# v5-Relay-Section-temp.net
KiCad netlist of a schematic drawn in EAGLE
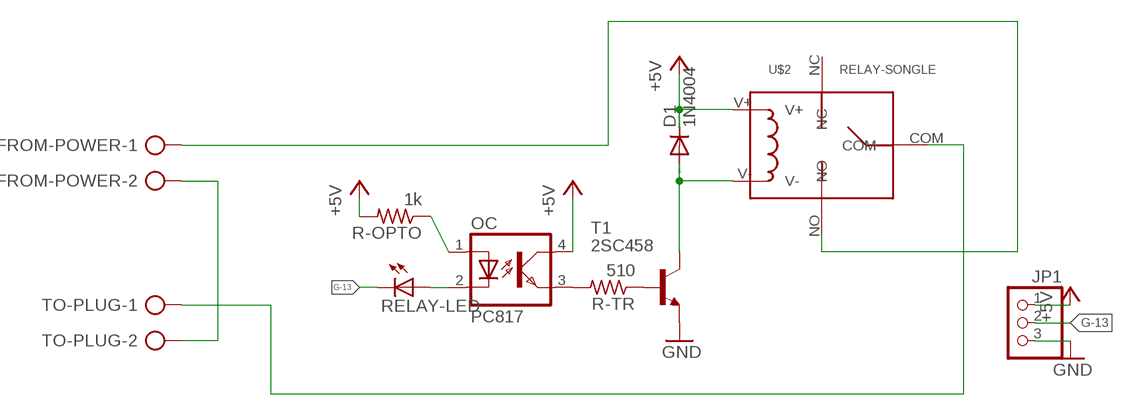
[diagram p0: schematic, sheet 1]

(export (version "E")
  (design (tool "Eeschema 10.0.6"))
  (components
    (comp (ref "D1")
      (value "1N4004")
      (footprint "eagle-import:DO41-10")
      (libsource (lib "eagle-import") (part "1N4004"))
    )
    (comp (ref "FROM-POWER")
      (value "AK300/2")
      (footprint "eagle-import:AK300_2")
      (libsource (lib "eagle-import") (part "AK300/2"))
    )
    (comp (ref "JP1")
      (value "PINHD-1X3")
      (footprint "eagle-import:1X03")
      (libsource (lib "eagle-import") (part "PINHD-1X3"))
    )
    (comp (ref "OC")
      (value "PC817")
      (footprint "eagle-import:DIL04")
      (fields (field (name "MPN") "PC817X4J000F"))
      (libsource (lib "eagle-import") (part "PC817"))
    )
    (comp (ref "R-OPTO")
      (value "1k")
      (footprint "eagle-import:0207_7")
      (libsource (lib "eagle-import") (part "R-US_0207/7"))
    )
    (comp (ref "R-TR")
      (value "510")
      (footprint "eagle-import:0207_7")
      (libsource (lib "eagle-import") (part "R-US_0207/7"))
    )
    (comp (ref "RELAY-LED")
      (value "LED3MM")
      (footprint "eagle-import:LED3MM")
      (libsource (lib "eagle-import") (part "LED3MM"))
    )
    (comp (ref "T1")
      (value "2SC458")
      (footprint "eagle-import:TO92-ECB")
      (libsource (lib "eagle-import") (part "2SC458"))
    )
    (comp (ref "TO-PLUG")
      (value "AK300/2")
      (footprint "eagle-import:AK300_2")
      (libsource (lib "eagle-import") (part "AK300/2"))
    )
    (comp (ref "U$2")
      (value "RELAY-SONGLE")
      (footprint "eagle-import:RELAY-SONGLE")
      (libsource (lib "eagle-import") (part "RELAY-SONGLE"))
    )
  )
  (nets
    (net (code "1") (name "+5V") (class "Default")
      (node (ref "D1") (pin "C") (pinfunction "C_C") (pintype "passive"))
      (node (ref "JP1") (pin "1") (pinfunction "1_1") (pintype "passive"))
      (node (ref "OC") (pin "4") (pinfunction "COL_4") (pintype "passive"))
      (node (ref "R-OPTO") (pin "2") (pinfunction "2_2") (pintype "passive"))
      (node (ref "U$2") (pin "V+") (pinfunction "V+_V+") (pintype "bidirectional"))
    )
    (net (code "2") (name "G-13") (class "Default")
      (node (ref "JP1") (pin "2") (pinfunction "2_2") (pintype "passive"))
      (node (ref "RELAY-LED") (pin "K") (pinfunction "C_K") (pintype "passive"))
    )
    (net (code "3") (name "GND") (class "Default")
      (node (ref "JP1") (pin "3") (pinfunction "3_3") (pintype "passive"))
      (node (ref "T1") (pin "E") (pinfunction "E_E") (pintype "passive"))
    )
    (net (code "4") (name "Net-(D1-PadA)") (class "Default")
      (node (ref "D1") (pin "A") (pinfunction "A_A") (pintype "passive"))
      (node (ref "T1") (pin "C") (pinfunction "C_C") (pintype "passive"))
      (node (ref "U$2") (pin "V-") (pinfunction "V-_V-") (pintype "bidirectional"))
    )
    (net (code "5") (name "Net-(FROM-POWERA-KL)") (class "Default")
      (node (ref "FROM-POWER") (pin "1") (pinfunction "KL_1") (pintype "passive"))
      (node (ref "U$2") (pin "NO") (pinfunction "NO_NO") (pintype "bidirectional"))
    )
    (net (code "6") (name "Net-(FROM-POWERB-KL)") (class "Default")
      (node (ref "FROM-POWER") (pin "2") (pinfunction "KL_2") (pintype "passive"))
      (node (ref "TO-PLUG") (pin "2") (pinfunction "KL_2") (pintype "passive"))
    )
    (net (code "7") (name "Net-(OC-A)") (class "Default")
      (node (ref "OC") (pin "1") (pinfunction "A_1") (pintype "passive"))
      (node (ref "R-OPTO") (pin "1") (pinfunction "1_1") (pintype "passive"))
    )
    (net (code "8") (name "Net-(OC-C)") (class "Default")
      (node (ref "OC") (pin "2") (pinfunction "C_2") (pintype "passive"))
      (node (ref "RELAY-LED") (pin "A") (pinfunction "A_A") (pintype "passive"))
    )
    (net (code "9") (name "Net-(OC-EMIT)") (class "Default")
      (node (ref "OC") (pin "3") (pinfunction "EMIT_3") (pintype "passive"))
      (node (ref "R-TR") (pin "2") (pinfunction "2_2") (pintype "passive"))
    )
    (net (code "10") (name "Net-(R-TR-Pad1)") (class "Default")
      (node (ref "R-TR") (pin "1") (pinfunction "1_1") (pintype "passive"))
      (node (ref "T1") (pin "B") (pinfunction "B_B") (pintype "passive"))
    )
    (net (code "11") (name "Net-(TO-PLUGA-KL)") (class "Default")
      (node (ref "TO-PLUG") (pin "1") (pinfunction "KL_1") (pintype "passive"))
      (node (ref "U$2") (pin "COM") (pinfunction "COM_COM") (pintype "bidirectional"))
    )
    (net (code "12") (name "unconnected-(U$2-PadNC)") (class "Default")
      (node (ref "U$2") (pin "NC") (pinfunction "NC_NC") (pintype "bidirectional"))
    )
  )
)
